# 03_-_CIRCUIT.net
KiCad netlist of a schematic drawn in Altium Designer
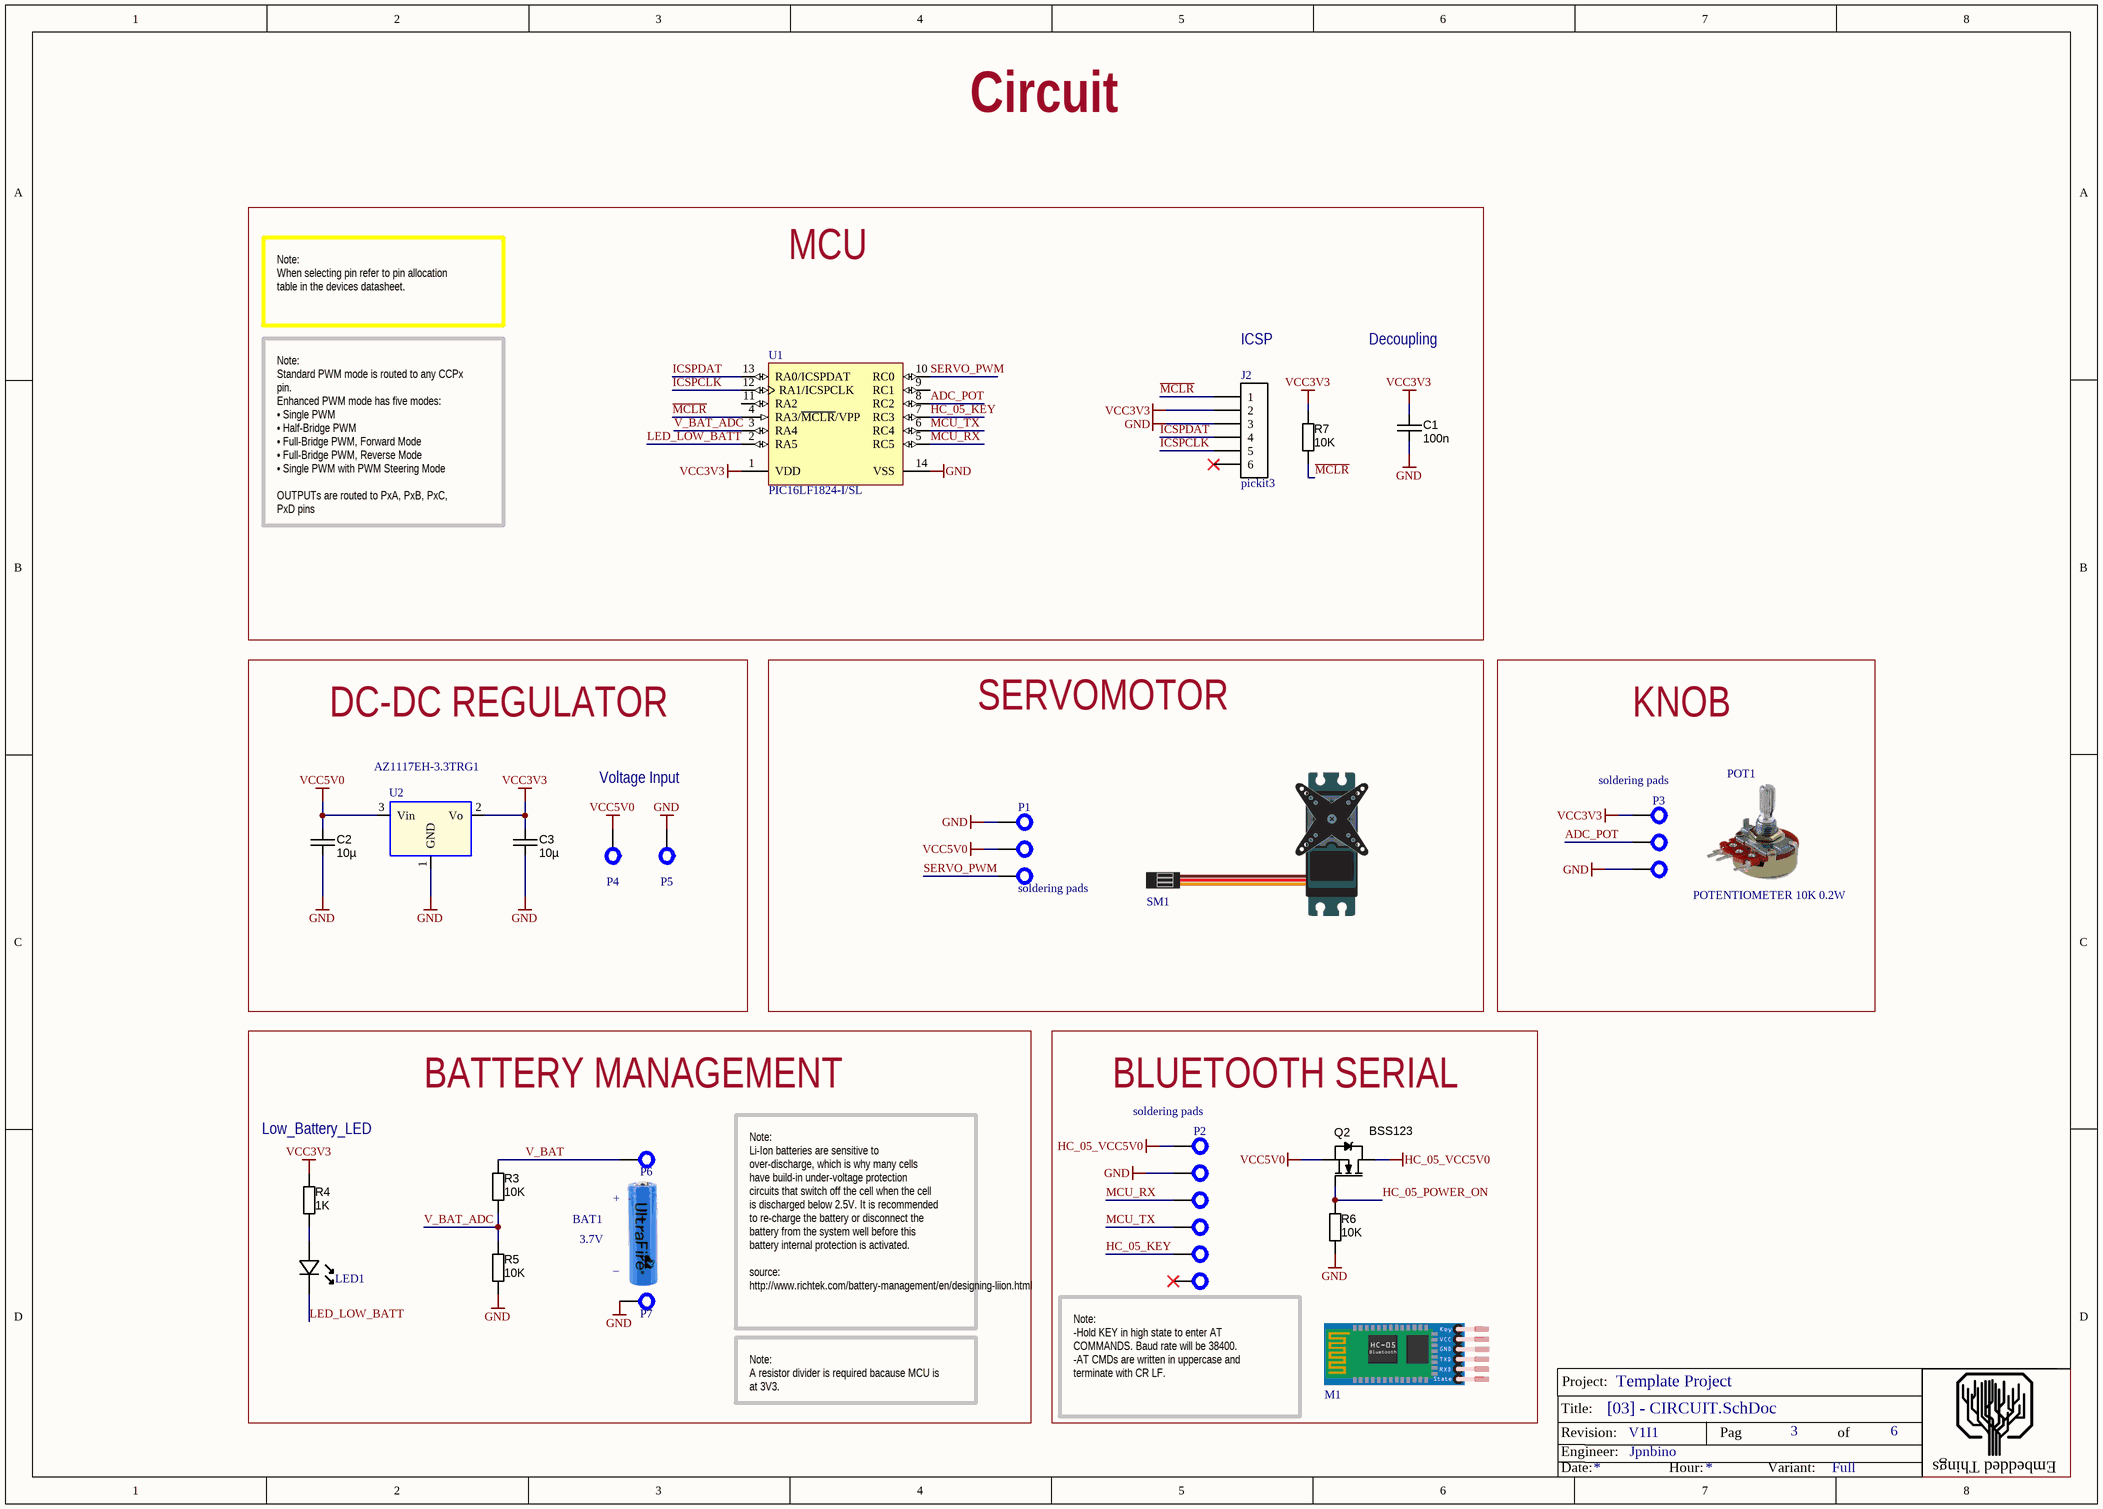
[diagram p0: [03] - CIRCUIT.SchDoc]

(export (version "E")
  (design (tool "Eeschema 10.0.6"))
  (components
    (comp (ref "BAT1")
      (value "3.7V")
      (description "Battery Li-Ion 3.7V 14500")
      (libsource (lib "jpnbino") (part "Battery Li-Ion 3.7V"))
    )
    (comp (ref "C1")
      (value "100n")
      (footprint "CAPC1608X90N")
      (description "Capacitor SMD Cer 100nF 10% 50V X7R 0603")
      (fields (field (name "TOLERANCE") "±10%") (field (name "Comment") "approved sub OK"))
      (libsource (lib "PBL - Capacitors") (part "CAPC_100n_0603_X7R_50V_10%"))
    )
    (comp (ref "C2")
      (value "10µ")
      (footprint "CAPC3216X180N")
      (description "Capacitor SMD Cer 10uF 10% 25V X7R 1206")
      (fields (field (name "TOLERANCE") "±10%") (field (name "Comment") "approved sub OK"))
      (libsource (lib "jpnbino") (part "CAPC_10u_1206_25V"))
    )
    (comp (ref "C3")
      (value "10µ")
      (footprint "CAPC3216X180N")
      (description "Capacitor SMD Cer 10uF 10% 25V X7R 1206")
      (fields (field (name "TOLERANCE") "±10%") (field (name "Comment") "approved sub OK"))
      (libsource (lib "jpnbino") (part "CAPC_10u_1206_25V"))
    )
    (comp (ref "J2")
      (value "pickit3")
      (footprint "CONN_ICSP")
      (description "CONN PROG PICKIT3 6VIAS")
      (libsource (lib "jpnbino") (part "CONN PROG PICKIT3"))
    )
    (comp (ref "LED1")
      (value "RED")
      (footprint "LED-0603-RED")
      (description "LED RED CLEAR 0603 SMD")
      (fields
        (field (name "MANUFACTURER") "Lite-On Inc.")
        (field (name "MANUFACTURER PART NUMBER") "LTST-C190KRKT")
      )
      (libsource (lib "jpnbino") (part "LED RED CLEAR 0603 SMD"))
    )
    (comp (ref "M1")
      (value "MODULE HC-05")
      (description "MODULE BLUETOOTH HC-05 JY-MCU")
      (libsource (lib "jpnbino") (part "MODULE HC-05"))
    )
    (comp (ref "P1")
      (value "3")
      (footprint "PAD_PTH 3 vias")
      (description "PAD PTH 3 VIAS HOLE 1MM PITCH2.54MM")
      (fields (field (name "TYPE") "soldering pads"))
      (libsource (lib "jpnbino") (part "PAD PTH 3 VIAS HOLE 1MM"))
    )
    (comp (ref "P2")
      (value "6")
      (footprint "PAD_PTH 6 VIAS")
      (description "PAD PTH 6 VIAS HOLE 1MM PITCH2.54MM")
      (fields (field (name "TYPE") "soldering pads"))
      (libsource (lib "jpnbino") (part "PAD PTH 6 VIAS HOLE 1MM"))
    )
    (comp (ref "P3")
      (value "3")
      (footprint "PAD_PTH 3 vias")
      (description "PAD PTH 3 VIAS HOLE 1MM PITCH2.54MM")
      (fields (field (name "TYPE") "soldering pads"))
      (libsource (lib "jpnbino") (part "PAD PTH 3 VIAS HOLE 1MM"))
    )
    (comp (ref "P4")
      (value "1")
      (footprint "PAD_PTH")
      (description "PAD PTH 1 VIA HOLE 1MM")
      (libsource (lib "jpnbino") (part "PAD PTH 1 VIA HOLE 1MM"))
    )
    (comp (ref "P5")
      (value "1")
      (footprint "PAD_PTH")
      (description "PAD PTH 1 VIA HOLE 1MM")
      (libsource (lib "jpnbino") (part "PAD PTH 1 VIA HOLE 1MM"))
    )
    (comp (ref "P6")
      (value "1")
      (footprint "PAD_PTH")
      (description "PAD PTH 1 VIA HOLE 1MM")
      (libsource (lib "jpnbino") (part "PAD PTH 1 VIA HOLE 1MM"))
    )
    (comp (ref "P7")
      (value "1")
      (footprint "PAD_PTH")
      (description "PAD PTH 1 VIA HOLE 1MM")
      (libsource (lib "jpnbino") (part "PAD PTH 1 VIA HOLE 1MM"))
    )
    (comp (ref "POT1")
      (value "POTENTIOMETER 10K 0.2W")
      (fields
        (field (name "MANUFACTURER") "TT Electronics/BI")
        (field (name "MANUFACTURER PART NUMBER") "P160KN2-4QC20B10K")
        (field (name "TOLERANCE") "±20%")
      )
      (libsource (lib "jpnbino") (part "POTENTIOMETER 10K 0.2W"))
    )
    (comp (ref "Q2")
      (value "BSS123")
      (footprint "SOT23-3")
      (description "MOSFET SMD N-CH 100V 170mA SOT23-3")
      (libsource (lib "PBL - Transistors") (part "MOSFET_BSS123"))
    )
    (comp (ref "R3")
      (value "10K")
      (footprint "RESC1608X55N")
      (description "Resistor SMD chip 10k Ohm 0.1W 5% 0603")
      (fields (field (name "TOLERANCE") "±5%") (field (name "Comment") "Thick Film"))
      (libsource (lib "PBL - Resistors") (part "RES_10K_0603_5%"))
    )
    (comp (ref "R4")
      (value "1K")
      (footprint "RESC1608X55N")
      (description "Resistor SMD chip 1k Ohm 0.1W 5% 0603")
      (fields (field (name "TOLERANCE") "±5%") (field (name "Comment") "Thick Film"))
      (libsource (lib "PBL - Resistors") (part "RES_1K_0603_5%"))
    )
    (comp (ref "R5")
      (value "10K")
      (footprint "RESC1608X55N")
      (description "Resistor SMD chip 10k Ohm 0.1W 5% 0603")
      (fields (field (name "TOLERANCE") "±5%") (field (name "Comment") "Thick Film"))
      (libsource (lib "PBL - Resistors") (part "RES_10K_0603_5%"))
    )
    (comp (ref "R6")
      (value "10K")
      (footprint "RESC1608X55N")
      (description "Resistor SMD chip 10k Ohm 0.1W 5% 0603")
      (fields (field (name "TOLERANCE") "±5%") (field (name "Comment") "Thick Film"))
      (libsource (lib "PBL - Resistors") (part "RES_10K_0603_5%"))
    )
    (comp (ref "R7")
      (value "10K")
      (footprint "RESC1608X55N")
      (description "Resistor SMD chip 10k Ohm 0.1W 5% 0603")
      (fields (field (name "TOLERANCE") "±5%") (field (name "Comment") "Thick Film"))
      (libsource (lib "PBL - Resistors") (part "RES_10K_0603_5%"))
    )
    (comp (ref "SM1") (value "SERVOMOTOR 9G") (libsource (lib "jpnbino") (part "SERVOMOTOR 9G")))
    (comp (ref "U1")
      (value "PIC16LF1824-I/SL")
      (footprint "MCHP-SOIC-SL14_N")
      (fields (field (name "MANUFACTURER") "Microchip"))
      (libsource (lib "Microchip PIC16 Part 1") (part "PIC16LF1824-I/SL"))
    )
    (comp (ref "U2")
      (value "3V3, 1A")
      (footprint "SOT223")
      (description "IC REG LDO 3.3V 1A SOT223")
      (fields
        (field (name "MANUFACTURER") "Diodes Incorporated")
        (field (name "MANUFACTURER PART NUMBER") "AZ1117EH-3.3TRG1")
      )
      (libsource (lib "jpnbino") (part "REG AZ1117CR-33"))
    )
  )
  (nets
    (net (code "1") (name "/ADC_POT") (class "Default")
      (node (ref "P3") (pin "2") (pinfunction "2_2") (pintype "passive"))
      (node (ref "U1") (pin "8") (pinfunction "RC2_8") (pintype "bidirectional"))
    )
    (net (code "2") (name "/HC_05_KEY") (class "Default")
      (node (ref "P2") (pin "5") (pinfunction "5_5") (pintype "passive"))
      (node (ref "U1") (pin "7") (pinfunction "RC3_7") (pintype "bidirectional"))
    )
    (net (code "3") (name "/HC_05_POWER_ON") (class "Default")
      (node (ref "Q2") (pin "1") (pinfunction "G_1") (pintype "passive"))
      (node (ref "R6") (pin "1") (pinfunction "1_1") (pintype "passive"))
    )
    (net (code "4") (name "/ICSPCLK") (class "Default")
      (node (ref "J2") (pin "5") (pinfunction "5_5") (pintype "passive"))
      (node (ref "U1") (pin "12") (pinfunction "RA1/ICSPCLK_12") (pintype "bidirectional"))
    )
    (net (code "5") (name "/ICSPDAT") (class "Default")
      (node (ref "J2") (pin "4") (pinfunction "4_4") (pintype "passive"))
      (node (ref "U1") (pin "13") (pinfunction "RA0/ICSPDAT_13") (pintype "bidirectional"))
    )
    (net (code "6") (name "/LED_LOW_BATT") (class "Default")
      (node (ref "LED1") (pin "K") (pinfunction "K_K") (pintype "passive"))
      (node (ref "U1") (pin "2") (pinfunction "RA5_2") (pintype "bidirectional"))
    )
    (net (code "7") (name "/MCU_RX") (class "Default")
      (node (ref "P2") (pin "3") (pinfunction "3_3") (pintype "passive"))
      (node (ref "U1") (pin "5") (pinfunction "RC5_5") (pintype "bidirectional"))
    )
    (net (code "8") (name "/MCU_TX") (class "Default")
      (node (ref "P2") (pin "4") (pinfunction "4_4") (pintype "passive"))
      (node (ref "U1") (pin "6") (pinfunction "RC4_6") (pintype "bidirectional"))
    )
    (net (code "9") (name "/SERVO_PWM") (class "Default")
      (node (ref "P1") (pin "3") (pinfunction "3_3") (pintype "passive"))
      (node (ref "U1") (pin "10") (pinfunction "RC0_10") (pintype "bidirectional"))
    )
    (net (code "10") (name "/V_BAT") (class "Default")
      (node (ref "P6") (pin "1") (pinfunction "1_1") (pintype "passive"))
      (node (ref "R3") (pin "1") (pinfunction "1_1") (pintype "passive"))
    )
    (net (code "11") (name "/V_BAT_ADC") (class "Default")
      (node (ref "R3") (pin "2") (pinfunction "2_2") (pintype "passive"))
      (node (ref "R5") (pin "1") (pinfunction "1_1") (pintype "passive"))
      (node (ref "U1") (pin "3") (pinfunction "RA4_3") (pintype "bidirectional"))
    )
    (net (code "12") (name "/~{MCLR}") (class "Default")
      (node (ref "J2") (pin "1") (pinfunction "1_1") (pintype "passive"))
      (node (ref "R7") (pin "2") (pinfunction "2_2") (pintype "passive"))
      (node (ref "U1") (pin "4") (pinfunction "RA3/~{MCLR}/VPP_4") (pintype "input"))
    )
    (net (code "13") (name "GND") (class "Default")
      (node (ref "C1") (pin "1") (pintype "passive"))
      (node (ref "C2") (pin "2") (pintype "passive"))
      (node (ref "C3") (pin "2") (pintype "passive"))
      (node (ref "J2") (pin "3") (pinfunction "3_3") (pintype "passive"))
      (node (ref "P1") (pin "1") (pinfunction "1_1") (pintype "passive"))
      (node (ref "P2") (pin "2") (pinfunction "2_2") (pintype "passive"))
      (node (ref "P3") (pin "3") (pinfunction "3_3") (pintype "passive"))
      (node (ref "P5") (pin "1") (pinfunction "1_1") (pintype "passive"))
      (node (ref "P7") (pin "1") (pinfunction "1_1") (pintype "passive"))
      (node (ref "R5") (pin "2") (pinfunction "2_2") (pintype "passive"))
      (node (ref "R6") (pin "2") (pinfunction "2_2") (pintype "passive"))
      (node (ref "U1") (pin "14") (pinfunction "VSS_14") (pintype "power_in"))
      (node (ref "U2") (pin "1") (pinfunction "GND_1") (pintype "passive"))
    )
    (net (code "14") (name "HC_05_VCC5V0") (class "Default")
      (node (ref "P2") (pin "1") (pinfunction "1_1") (pintype "passive"))
      (node (ref "Q2") (pin "3") (pinfunction "D_3") (pintype "passive"))
    )
    (net (code "15") (name "Net-(LED1-PadA)") (class "Default")
      (node (ref "LED1") (pin "A") (pinfunction "A_A") (pintype "passive"))
      (node (ref "R4") (pin "2") (pinfunction "2_2") (pintype "passive"))
    )
    (net (code "16") (name "VCC3V3") (class "Default")
      (node (ref "C1") (pin "2") (pintype "passive"))
      (node (ref "C3") (pin "1") (pintype "passive"))
      (node (ref "J2") (pin "2") (pinfunction "2_2") (pintype "passive"))
      (node (ref "P3") (pin "1") (pinfunction "1_1") (pintype "passive"))
      (node (ref "R4") (pin "1") (pinfunction "1_1") (pintype "passive"))
      (node (ref "R7") (pin "1") (pinfunction "1_1") (pintype "passive"))
      (node (ref "U1") (pin "1") (pinfunction "VDD_1") (pintype "power_in"))
      (node (ref "U2") (pin "2") (pinfunction "Vo_2") (pintype "passive"))
    )
    (net (code "17") (name "VCC5V0") (class "Default")
      (node (ref "C2") (pin "1") (pintype "passive"))
      (node (ref "P1") (pin "2") (pinfunction "2_2") (pintype "passive"))
      (node (ref "P4") (pin "1") (pinfunction "1_1") (pintype "passive"))
      (node (ref "Q2") (pin "2") (pinfunction "S_2") (pintype "passive"))
      (node (ref "U2") (pin "3") (pinfunction "Vin_3") (pintype "passive"))
    )
    (net (code "18") (name "unconnected-(J2-Pad6)") (class "Default")
      (node (ref "J2") (pin "6") (pinfunction "6_6") (pintype "passive+no_connect"))
    )
    (net (code "19") (name "unconnected-(P2-Pad6)") (class "Default")
      (node (ref "P2") (pin "6") (pinfunction "6_6") (pintype "passive+no_connect"))
    )
    (net (code "20") (name "unconnected-(U1-RA2-Pad11)") (class "Default")
      (node (ref "U1") (pin "11") (pinfunction "RA2_11") (pintype "bidirectional"))
    )
    (net (code "21") (name "unconnected-(U1-RC1-Pad9)") (class "Default")
      (node (ref "U1") (pin "9") (pinfunction "RC1_9") (pintype "bidirectional"))
    )
    (net (code "22") (name "unconnected-(U2-Pad4)") (class "Default")
      (node (ref "U2") (pin "4") (pinfunction "4_4") (pintype "passive"))
    )
  )
)
